# HackJrGameController-v1_0.net
KiCad netlist of a schematic drawn in EAGLE
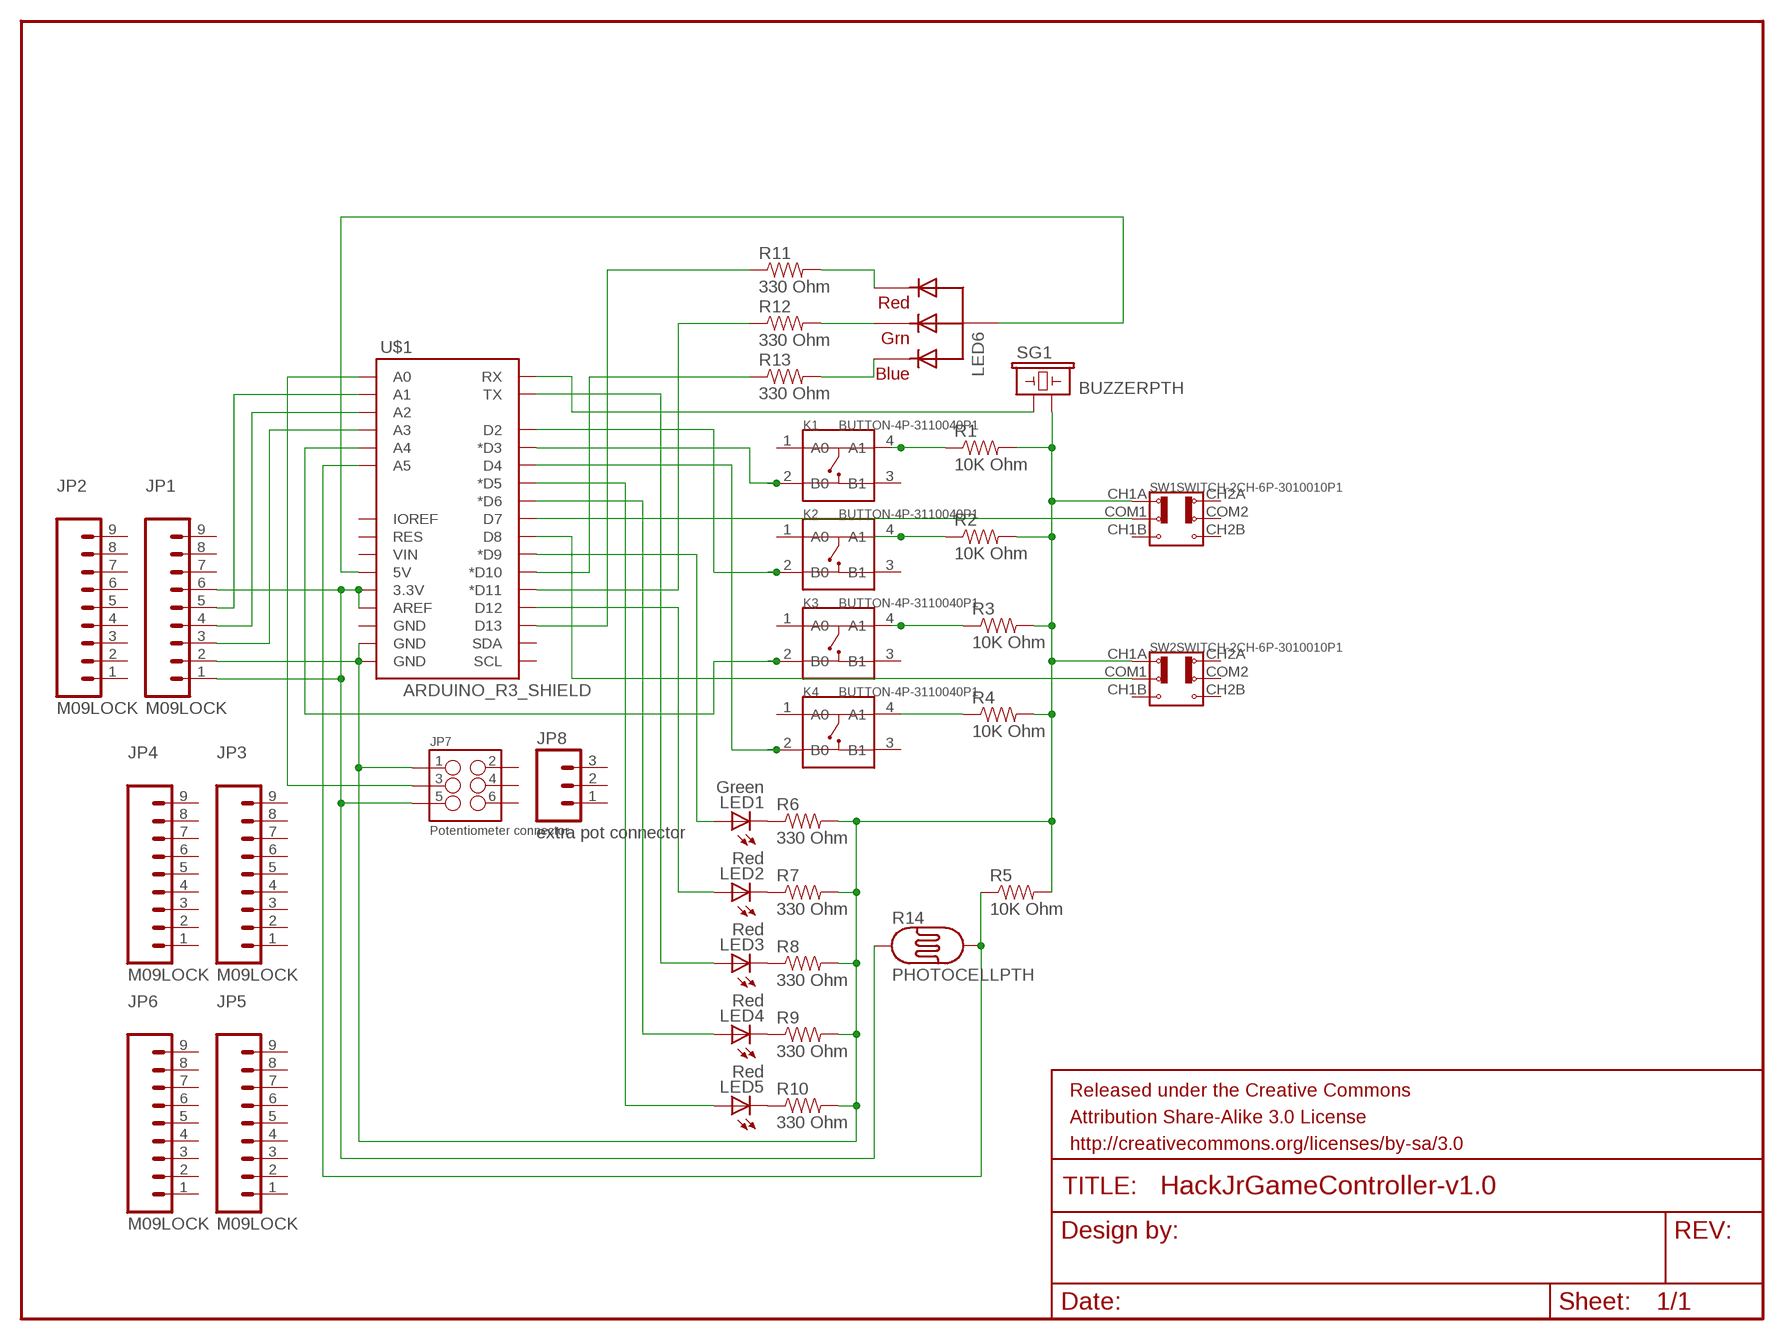
[diagram p0: schematic, sheet 1]

(export (version "E")
  (design (tool "Eeschema 10.0.6"))
  (components
    (comp (ref "FRAME1")
      (value "FRAME-LETTER")
      (footprint "eagle-import:CREATIVE_COMMONS")
      (libsource (lib "eagle-import") (part "FRAME-LETTER"))
    )
    (comp (ref "JP1")
      (value "M09LOCK")
      (footprint "eagle-import:1X09_LOCK")
      (libsource (lib "eagle-import") (part "M09LOCK"))
    )
    (comp (ref "JP2")
      (value "M09LOCK")
      (footprint "eagle-import:1X09_LOCK")
      (libsource (lib "eagle-import") (part "M09LOCK"))
    )
    (comp (ref "JP3")
      (value "M09LOCK")
      (footprint "eagle-import:1X09_LOCK")
      (libsource (lib "eagle-import") (part "M09LOCK"))
    )
    (comp (ref "JP4")
      (value "M09LOCK")
      (footprint "eagle-import:1X09_LOCK")
      (libsource (lib "eagle-import") (part "M09LOCK"))
    )
    (comp (ref "JP5")
      (value "M09LOCK")
      (footprint "eagle-import:1X09_LOCK")
      (libsource (lib "eagle-import") (part "M09LOCK"))
    )
    (comp (ref "JP6")
      (value "M09LOCK")
      (footprint "eagle-import:1X09_LOCK")
      (libsource (lib "eagle-import") (part "M09LOCK"))
    )
    (comp (ref "JP7")
      (value "Potentiometer connector")
      (footprint "eagle-import:2X3-NS")
      (libsource (lib "eagle-import") (part "M03X2NO_SILK"))
    )
    (comp (ref "JP8")
      (value "extra pot connector")
      (footprint "eagle-import:1X03_NO_SILK")
      (libsource (lib "eagle-import") (part "M031X03_NO_SILK"))
    )
    (comp (ref "K1")
      (value "BUTTON-4P-3110040P1")
      (footprint "eagle-import:4P-6.0X6.0X5.0H")
      (libsource (lib "eagle-import") (part "BUTTON-4P-3110040P1"))
    )
    (comp (ref "K2")
      (value "BUTTON-4P-3110040P1")
      (footprint "eagle-import:4P-6.0X6.0X5.0H")
      (libsource (lib "eagle-import") (part "BUTTON-4P-3110040P1"))
    )
    (comp (ref "K3")
      (value "BUTTON-4P-3110040P1")
      (footprint "eagle-import:4P-6.0X6.0X5.0H")
      (libsource (lib "eagle-import") (part "BUTTON-4P-3110040P1"))
    )
    (comp (ref "K4")
      (value "BUTTON-4P-3110040P1")
      (footprint "eagle-import:4P-6.0X6.0X5.0H")
      (libsource (lib "eagle-import") (part "BUTTON-4P-3110040P1"))
    )
    (comp (ref "LED1")
      (value "Green")
      (footprint "eagle-import:LED5MM")
      (libsource (lib "eagle-import") (part "LED5MM"))
    )
    (comp (ref "LED2")
      (value "Red")
      (footprint "eagle-import:LED5MM")
      (libsource (lib "eagle-import") (part "LED5MM"))
    )
    (comp (ref "LED3")
      (value "Red")
      (footprint "eagle-import:LED5MM")
      (libsource (lib "eagle-import") (part "LED5MM"))
    )
    (comp (ref "LED4")
      (value "Red")
      (footprint "eagle-import:LED5MM")
      (libsource (lib "eagle-import") (part "LED5MM"))
    )
    (comp (ref "LED5")
      (value "Red")
      (footprint "eagle-import:LED5MM")
      (libsource (lib "eagle-import") (part "LED5MM"))
    )
    (comp (ref "LED6")
      (value "RGBLED_CA-5MM")
      (footprint "eagle-import:LED5MMRGB")
      (libsource (lib "eagle-import") (part "RGBLED_CA-5MM"))
    )
    (comp (ref "R1")
      (value "10K Ohm")
      (footprint "eagle-import:AXIAL-0.3-KIT")
      (libsource (lib "eagle-import") (part "10KOHM1/6W5%(PTH)KIT"))
    )
    (comp (ref "R2")
      (value "10K Ohm")
      (footprint "eagle-import:AXIAL-0.3-KIT")
      (libsource (lib "eagle-import") (part "10KOHM1/6W5%(PTH)KIT"))
    )
    (comp (ref "R3")
      (value "10K Ohm")
      (footprint "eagle-import:AXIAL-0.3-KIT")
      (libsource (lib "eagle-import") (part "10KOHM1/6W5%(PTH)KIT"))
    )
    (comp (ref "R4")
      (value "10K Ohm")
      (footprint "eagle-import:AXIAL-0.3-KIT")
      (libsource (lib "eagle-import") (part "10KOHM1/6W5%(PTH)KIT"))
    )
    (comp (ref "R5")
      (value "10K Ohm")
      (footprint "eagle-import:AXIAL-0.3-KIT")
      (libsource (lib "eagle-import") (part "10KOHM1/6W5%(PTH)KIT"))
    )
    (comp (ref "R6")
      (value "330 Ohm")
      (footprint "eagle-import:AXIAL-0.3-KIT")
      (libsource (lib "eagle-import") (part "RESISTORKIT"))
    )
    (comp (ref "R7")
      (value "330 Ohm")
      (footprint "eagle-import:AXIAL-0.3-KIT")
      (libsource (lib "eagle-import") (part "RESISTORKIT"))
    )
    (comp (ref "R8")
      (value "330 Ohm")
      (footprint "eagle-import:AXIAL-0.3-KIT")
      (libsource (lib "eagle-import") (part "RESISTORKIT"))
    )
    (comp (ref "R9")
      (value "330 Ohm")
      (footprint "eagle-import:AXIAL-0.3-KIT")
      (libsource (lib "eagle-import") (part "RESISTORKIT"))
    )
    (comp (ref "R10")
      (value "330 Ohm")
      (footprint "eagle-import:AXIAL-0.3-KIT")
      (libsource (lib "eagle-import") (part "RESISTORKIT"))
    )
    (comp (ref "R11")
      (value "330 Ohm")
      (footprint "eagle-import:AXIAL-0.3-KIT")
      (libsource (lib "eagle-import") (part "RESISTORKIT"))
    )
    (comp (ref "R12")
      (value "330 Ohm")
      (footprint "eagle-import:AXIAL-0.3-KIT")
      (libsource (lib "eagle-import") (part "RESISTORKIT"))
    )
    (comp (ref "R13")
      (value "330 Ohm")
      (footprint "eagle-import:AXIAL-0.3-KIT")
      (libsource (lib "eagle-import") (part "RESISTORKIT"))
    )
    (comp (ref "R14")
      (value "PHOTOCELLPTH")
      (footprint "eagle-import:PHOTOCELL")
      (libsource (lib "eagle-import") (part "PHOTOCELLPTH"))
    )
    (comp (ref "SG1")
      (value "BUZZERPTH")
      (footprint "eagle-import:BUZZER-12MM")
      (libsource (lib "eagle-import") (part "BUZZERPTH"))
    )
    (comp (ref "SW1")
      (value "SWITCH-2CH-6P-3010010P1")
      (footprint "eagle-import:6P-2CH-2.54-9.1X3.5X3.2+2H")
      (libsource (lib "eagle-import") (part "SWITCH-2CH-6P-3010010P1"))
    )
    (comp (ref "SW2")
      (value "SWITCH-2CH-6P-3010010P1")
      (footprint "eagle-import:6P-2CH-2.54-9.1X3.5X3.2+2H")
      (libsource (lib "eagle-import") (part "SWITCH-2CH-6P-3010010P1"))
    )
    (comp (ref "U$1")
      (value "ARDUINO_R3_SHIELD")
      (footprint "eagle-import:UNO_R3_SHIELD")
      (libsource (lib "eagle-import") (part "ARDUINO_R3_SHIELD"))
    )
  )
  (nets
    (net (code "1") (name "Net-(JP1-Pad3)") (class "Default")
      (node (ref "JP1") (pin "3") (pinfunction "3_3") (pintype "passive"))
      (node (ref "U$1") (pin "A3") (pinfunction "A3_A3") (pintype "bidirectional"))
    )
    (net (code "2") (name "Net-(JP1-Pad4)") (class "Default")
      (node (ref "JP1") (pin "4") (pinfunction "4_4") (pintype "passive"))
      (node (ref "U$1") (pin "A2") (pinfunction "A2_A2") (pintype "bidirectional"))
    )
    (net (code "3") (name "Net-(JP1-Pad5)") (class "Default")
      (node (ref "JP1") (pin "5") (pinfunction "5_5") (pintype "passive"))
      (node (ref "U$1") (pin "A1") (pinfunction "A1_A1") (pintype "bidirectional"))
    )
    (net (code "4") (name "Net-(JP7-Pad3)") (class "Default")
      (node (ref "JP7") (pin "3") (pinfunction "3_3") (pintype "bidirectional"))
      (node (ref "U$1") (pin "A0") (pinfunction "A0_A0") (pintype "bidirectional"))
    )
    (net (code "5") (name "Net-(K1-A1)") (class "Default")
      (node (ref "K1") (pin "4") (pinfunction "A1_4") (pintype "bidirectional"))
      (node (ref "R1") (pin "P$1") (pinfunction "1_P$1") (pintype "passive"))
    )
    (net (code "6") (name "Net-(K1-B0)") (class "Default")
      (node (ref "K1") (pin "2") (pinfunction "B0_2") (pintype "bidirectional"))
      (node (ref "U$1") (pin "D3") (pinfunction "*D3_D3") (pintype "bidirectional"))
    )
    (net (code "7") (name "Net-(K2-A1)") (class "Default")
      (node (ref "K2") (pin "4") (pinfunction "A1_4") (pintype "bidirectional"))
      (node (ref "R2") (pin "P$1") (pinfunction "1_P$1") (pintype "passive"))
    )
    (net (code "8") (name "Net-(K2-B0)") (class "Default")
      (node (ref "K2") (pin "2") (pinfunction "B0_2") (pintype "bidirectional"))
      (node (ref "U$1") (pin "D2") (pinfunction "D2_D2") (pintype "bidirectional"))
    )
    (net (code "9") (name "Net-(K3-A1)") (class "Default")
      (node (ref "K3") (pin "4") (pinfunction "A1_4") (pintype "bidirectional"))
      (node (ref "R3") (pin "P$1") (pinfunction "1_P$1") (pintype "passive"))
    )
    (net (code "10") (name "Net-(K3-B0)") (class "Default")
      (node (ref "K3") (pin "2") (pinfunction "B0_2") (pintype "bidirectional"))
      (node (ref "U$1") (pin "A4") (pinfunction "A4_A4") (pintype "bidirectional"))
    )
    (net (code "11") (name "Net-(K4-A1)") (class "Default")
      (node (ref "K4") (pin "4") (pinfunction "A1_4") (pintype "bidirectional"))
      (node (ref "R4") (pin "P$1") (pinfunction "1_P$1") (pintype "passive"))
    )
    (net (code "12") (name "Net-(K4-B0)") (class "Default")
      (node (ref "K4") (pin "2") (pinfunction "B0_2") (pintype "bidirectional"))
      (node (ref "U$1") (pin "D4") (pinfunction "D4_D4") (pintype "bidirectional"))
    )
    (net (code "13") (name "Net-(LED1-C)") (class "Default")
      (node (ref "LED1") (pin "K") (pinfunction "C_K") (pintype "passive"))
      (node (ref "R6") (pin "P$1") (pinfunction "1_P$1") (pintype "passive"))
    )
    (net (code "14") (name "Net-(LED2-C)") (class "Default")
      (node (ref "LED2") (pin "K") (pinfunction "C_K") (pintype "passive"))
      (node (ref "R7") (pin "P$1") (pinfunction "1_P$1") (pintype "passive"))
    )
    (net (code "15") (name "Net-(LED2-PadA)") (class "Default")
      (node (ref "LED2") (pin "A") (pinfunction "A_A") (pintype "passive"))
      (node (ref "U$1") (pin "D12") (pinfunction "D12_D12") (pintype "bidirectional"))
    )
    (net (code "16") (name "Net-(LED3-C)") (class "Default")
      (node (ref "LED3") (pin "K") (pinfunction "C_K") (pintype "passive"))
      (node (ref "R8") (pin "P$1") (pinfunction "1_P$1") (pintype "passive"))
    )
    (net (code "17") (name "Net-(LED3-PadA)") (class "Default")
      (node (ref "LED3") (pin "A") (pinfunction "A_A") (pintype "passive"))
      (node (ref "U$1") (pin "TX") (pinfunction "TX_TX") (pintype "bidirectional"))
    )
    (net (code "18") (name "Net-(LED4-C)") (class "Default")
      (node (ref "LED4") (pin "K") (pinfunction "C_K") (pintype "passive"))
      (node (ref "R9") (pin "P$1") (pinfunction "1_P$1") (pintype "passive"))
    )
    (net (code "19") (name "Net-(LED5-C)") (class "Default")
      (node (ref "LED5") (pin "K") (pinfunction "C_K") (pintype "passive"))
      (node (ref "R10") (pin "P$1") (pinfunction "1_P$1") (pintype "passive"))
    )
    (net (code "20") (name "Net-(LED6-BLUE)") (class "Default")
      (node (ref "LED6") (pin "4") (pinfunction "BLUE_4") (pintype "bidirectional"))
      (node (ref "R13") (pin "P$2") (pinfunction "2_P$2") (pintype "passive"))
    )
    (net (code "21") (name "Net-(LED6-GREEN)") (class "Default")
      (node (ref "LED6") (pin "3") (pinfunction "GREEN_3") (pintype "bidirectional"))
      (node (ref "R12") (pin "P$2") (pinfunction "2_P$2") (pintype "passive"))
    )
    (net (code "22") (name "Net-(LED6-RED)") (class "Default")
      (node (ref "LED6") (pin "1") (pinfunction "RED_1") (pintype "bidirectional"))
      (node (ref "R11") (pin "P$2") (pinfunction "2_P$2") (pintype "passive"))
    )
    (net (code "23") (name "Net-(LED6-VCC)") (class "Default")
      (node (ref "LED6") (pin "2") (pinfunction "VCC_2") (pintype "bidirectional"))
      (node (ref "U$1") (pin "5V") (pinfunction "5V_5V") (pintype "bidirectional"))
    )
    (net (code "24") (name "Net-(R1-2)") (class "Default")
      (node (ref "JP1") (pin "2") (pinfunction "2_2") (pintype "passive"))
      (node (ref "JP7") (pin "1") (pinfunction "1_1") (pintype "bidirectional"))
      (node (ref "R1") (pin "P$2") (pinfunction "2_P$2") (pintype "passive"))
      (node (ref "R10") (pin "P$2") (pinfunction "2_P$2") (pintype "passive"))
      (node (ref "R2") (pin "P$2") (pinfunction "2_P$2") (pintype "passive"))
      (node (ref "R3") (pin "P$2") (pinfunction "2_P$2") (pintype "passive"))
      (node (ref "R4") (pin "P$2") (pinfunction "2_P$2") (pintype "passive"))
      (node (ref "R5") (pin "P$2") (pinfunction "2_P$2") (pintype "passive"))
      (node (ref "R6") (pin "P$2") (pinfunction "2_P$2") (pintype "passive"))
      (node (ref "R7") (pin "P$2") (pinfunction "2_P$2") (pintype "passive"))
      (node (ref "R8") (pin "P$2") (pinfunction "2_P$2") (pintype "passive"))
      (node (ref "R9") (pin "P$2") (pinfunction "2_P$2") (pintype "passive"))
      (node (ref "SG1") (pin "-") (pinfunction "2_-") (pintype "passive"))
      (node (ref "SW1") (pin "CH1A") (pinfunction "CH1A_CH1A") (pintype "bidirectional"))
      (node (ref "SW2") (pin "CH1A") (pinfunction "CH1A_CH1A") (pintype "bidirectional"))
      (node (ref "U$1") (pin "GND@0") (pinfunction "GND_GND@0") (pintype "bidirectional"))
      (node (ref "U$1") (pin "GND@1") (pinfunction "GND_GND@1") (pintype "bidirectional"))
    )
    (net (code "25") (name "Net-(R11-1)") (class "Default")
      (node (ref "R11") (pin "P$1") (pinfunction "1_P$1") (pintype "passive"))
      (node (ref "U$1") (pin "D13") (pinfunction "D13_D13") (pintype "bidirectional"))
    )
    (net (code "26") (name "Net-(R12-1)") (class "Default")
      (node (ref "R12") (pin "P$1") (pinfunction "1_P$1") (pintype "passive"))
      (node (ref "U$1") (pin "D11") (pinfunction "*D11_D11") (pintype "bidirectional"))
    )
    (net (code "27") (name "Net-(R13-1)") (class "Default")
      (node (ref "R13") (pin "P$1") (pinfunction "1_P$1") (pintype "passive"))
      (node (ref "U$1") (pin "D10") (pinfunction "*D10_D10") (pintype "bidirectional"))
    )
    (net (code "28") (name "Net-(R14-P$1)") (class "Default")
      (node (ref "JP1") (pin "1") (pinfunction "1_1") (pintype "passive"))
      (node (ref "JP1") (pin "6") (pinfunction "6_6") (pintype "passive"))
      (node (ref "JP7") (pin "5") (pinfunction "5_5") (pintype "bidirectional"))
      (node (ref "R14") (pin "1") (pinfunction "P$1_1") (pintype "bidirectional"))
      (node (ref "U$1") (pin "3.3V") (pinfunction "3.3V_3.3V") (pintype "bidirectional"))
      (node (ref "U$1") (pin "AREF") (pinfunction "AREF_AREF") (pintype "bidirectional"))
    )
    (net (code "29") (name "Net-(R14-P$2)") (class "Default")
      (node (ref "R14") (pin "2") (pinfunction "P$2_2") (pintype "bidirectional"))
      (node (ref "R5") (pin "P$1") (pinfunction "1_P$1") (pintype "passive"))
      (node (ref "U$1") (pin "A5") (pinfunction "A5_A5") (pintype "bidirectional"))
    )
    (net (code "30") (name "Net-(SG1-1)") (class "Default")
      (node (ref "SG1") (pin "+") (pinfunction "1_+") (pintype "passive"))
      (node (ref "U$1") (pin "RX") (pinfunction "RX_RX") (pintype "bidirectional"))
    )
    (net (code "31") (name "Net-(SW1-PadCOM1)") (class "Default")
      (node (ref "SW1") (pin "COM1") (pinfunction "COM1_COM1") (pintype "bidirectional"))
      (node (ref "U$1") (pin "D7") (pinfunction "D7_D7") (pintype "bidirectional"))
    )
    (net (code "32") (name "Net-(SW2-PadCOM1)") (class "Default")
      (node (ref "SW2") (pin "COM1") (pinfunction "COM1_COM1") (pintype "bidirectional"))
      (node (ref "U$1") (pin "D8") (pinfunction "D8_D8") (pintype "bidirectional"))
    )
    (net (code "33") (name "Net-(U$1-*D5)") (class "Default")
      (node (ref "LED5") (pin "A") (pinfunction "A_A") (pintype "passive"))
      (node (ref "U$1") (pin "D5") (pinfunction "*D5_D5") (pintype "bidirectional"))
    )
    (net (code "34") (name "Net-(U$1-*D6)") (class "Default")
      (node (ref "LED4") (pin "A") (pinfunction "A_A") (pintype "passive"))
      (node (ref "U$1") (pin "D6") (pinfunction "*D6_D6") (pintype "bidirectional"))
    )
    (net (code "35") (name "Net-(U$1-*D9)") (class "Default")
      (node (ref "LED1") (pin "A") (pinfunction "A_A") (pintype "passive"))
      (node (ref "U$1") (pin "D9") (pinfunction "*D9_D9") (pintype "bidirectional"))
    )
    (net (code "36") (name "unconnected-(JP1-Pad7)") (class "Default")
      (node (ref "JP1") (pin "7") (pinfunction "7_7") (pintype "passive"))
    )
    (net (code "37") (name "unconnected-(JP1-Pad8)") (class "Default")
      (node (ref "JP1") (pin "8") (pinfunction "8_8") (pintype "passive"))
    )
    (net (code "38") (name "unconnected-(JP1-Pad9)") (class "Default")
      (node (ref "JP1") (pin "9") (pinfunction "9_9") (pintype "passive"))
    )
    (net (code "39") (name "unconnected-(JP2-Pad1)") (class "Default")
      (node (ref "JP2") (pin "1") (pinfunction "1_1") (pintype "passive"))
    )
    (net (code "40") (name "unconnected-(JP2-Pad2)") (class "Default")
      (node (ref "JP2") (pin "2") (pinfunction "2_2") (pintype "passive"))
    )
    (net (code "41") (name "unconnected-(JP2-Pad3)") (class "Default")
      (node (ref "JP2") (pin "3") (pinfunction "3_3") (pintype "passive"))
    )
    (net (code "42") (name "unconnected-(JP2-Pad4)") (class "Default")
      (node (ref "JP2") (pin "4") (pinfunction "4_4") (pintype "passive"))
    )
    (net (code "43") (name "unconnected-(JP2-Pad5)") (class "Default")
      (node (ref "JP2") (pin "5") (pinfunction "5_5") (pintype "passive"))
    )
    (net (code "44") (name "unconnected-(JP2-Pad6)") (class "Default")
      (node (ref "JP2") (pin "6") (pinfunction "6_6") (pintype "passive"))
    )
    (net (code "45") (name "unconnected-(JP2-Pad7)") (class "Default")
      (node (ref "JP2") (pin "7") (pinfunction "7_7") (pintype "passive"))
    )
    (net (code "46") (name "unconnected-(JP2-Pad8)") (class "Default")
      (node (ref "JP2") (pin "8") (pinfunction "8_8") (pintype "passive"))
    )
    (net (code "47") (name "unconnected-(JP2-Pad9)") (class "Default")
      (node (ref "JP2") (pin "9") (pinfunction "9_9") (pintype "passive"))
    )
    (net (code "48") (name "unconnected-(JP3-Pad1)") (class "Default")
      (node (ref "JP3") (pin "1") (pinfunction "1_1") (pintype "passive"))
    )
    (net (code "49") (name "unconnected-(JP3-Pad2)") (class "Default")
      (node (ref "JP3") (pin "2") (pinfunction "2_2") (pintype "passive"))
    )
    (net (code "50") (name "unconnected-(JP3-Pad3)") (class "Default")
      (node (ref "JP3") (pin "3") (pinfunction "3_3") (pintype "passive"))
    )
    (net (code "51") (name "unconnected-(JP3-Pad4)") (class "Default")
      (node (ref "JP3") (pin "4") (pinfunction "4_4") (pintype "passive"))
    )
    (net (code "52") (name "unconnected-(JP3-Pad5)") (class "Default")
      (node (ref "JP3") (pin "5") (pinfunction "5_5") (pintype "passive"))
    )
    (net (code "53") (name "unconnected-(JP3-Pad6)") (class "Default")
      (node (ref "JP3") (pin "6") (pinfunction "6_6") (pintype "passive"))
    )
    (net (code "54") (name "unconnected-(JP3-Pad7)") (class "Default")
      (node (ref "JP3") (pin "7") (pinfunction "7_7") (pintype "passive"))
    )
    (net (code "55") (name "unconnected-(JP3-Pad8)") (class "Default")
      (node (ref "JP3") (pin "8") (pinfunction "8_8") (pintype "passive"))
    )
    (net (code "56") (name "unconnected-(JP3-Pad9)") (class "Default")
      (node (ref "JP3") (pin "9") (pinfunction "9_9") (pintype "passive"))
    )
    (net (code "57") (name "unconnected-(JP4-Pad1)") (class "Default")
      (node (ref "JP4") (pin "1") (pinfunction "1_1") (pintype "passive"))
    )
    (net (code "58") (name "unconnected-(JP4-Pad2)") (class "Default")
      (node (ref "JP4") (pin "2") (pinfunction "2_2") (pintype "passive"))
    )
    (net (code "59") (name "unconnected-(JP4-Pad3)") (class "Default")
      (node (ref "JP4") (pin "3") (pinfunction "3_3") (pintype "passive"))
    )
    (net (code "60") (name "unconnected-(JP4-Pad4)") (class "Default")
      (node (ref "JP4") (pin "4") (pinfunction "4_4") (pintype "passive"))
    )
    (net (code "61") (name "unconnected-(JP4-Pad5)") (class "Default")
      (node (ref "JP4") (pin "5") (pinfunction "5_5") (pintype "passive"))
    )
    (net (code "62") (name "unconnected-(JP4-Pad6)") (class "Default")
      (node (ref "JP4") (pin "6") (pinfunction "6_6") (pintype "passive"))
    )
    (net (code "63") (name "unconnected-(JP4-Pad7)") (class "Default")
      (node (ref "JP4") (pin "7") (pinfunction "7_7") (pintype "passive"))
    )
    (net (code "64") (name "unconnected-(JP4-Pad8)") (class "Default")
      (node (ref "JP4") (pin "8") (pinfunction "8_8") (pintype "passive"))
    )
    (net (code "65") (name "unconnected-(JP4-Pad9)") (class "Default")
      (node (ref "JP4") (pin "9") (pinfunction "9_9") (pintype "passive"))
    )
    (net (code "66") (name "unconnected-(JP5-Pad1)") (class "Default")
      (node (ref "JP5") (pin "1") (pinfunction "1_1") (pintype "passive"))
    )
    (net (code "67") (name "unconnected-(JP5-Pad2)") (class "Default")
      (node (ref "JP5") (pin "2") (pinfunction "2_2") (pintype "passive"))
    )
    (net (code "68") (name "unconnected-(JP5-Pad3)") (class "Default")
      (node (ref "JP5") (pin "3") (pinfunction "3_3") (pintype "passive"))
    )
    (net (code "69") (name "unconnected-(JP5-Pad4)") (class "Default")
      (node (ref "JP5") (pin "4") (pinfunction "4_4") (pintype "passive"))
    )
    (net (code "70") (name "unconnected-(JP5-Pad5)") (class "Default")
      (node (ref "JP5") (pin "5") (pinfunction "5_5") (pintype "passive"))
    )
    (net (code "71") (name "unconnected-(JP5-Pad6)") (class "Default")
      (node (ref "JP5") (pin "6") (pinfunction "6_6") (pintype "passive"))
    )
    (net (code "72") (name "unconnected-(JP5-Pad7)") (class "Default")
      (node (ref "JP5") (pin "7") (pinfunction "7_7") (pintype "passive"))
    )
    (net (code "73") (name "unconnected-(JP5-Pad8)") (class "Default")
      (node (ref "JP5") (pin "8") (pinfunction "8_8") (pintype "passive"))
    )
    (net (code "74") (name "unconnected-(JP5-Pad9)") (class "Default")
      (node (ref "JP5") (pin "9") (pinfunction "9_9") (pintype "passive"))
    )
    (net (code "75") (name "unconnected-(JP6-Pad1)") (class "Default")
      (node (ref "JP6") (pin "1") (pinfunction "1_1") (pintype "passive"))
    )
    (net (code "76") (name "unconnected-(JP6-Pad2)") (class "Default")
      (node (ref "JP6") (pin "2") (pinfunction "2_2") (pintype "passive"))
    )
    (net (code "77") (name "unconnected-(JP6-Pad3)") (class "Default")
      (node (ref "JP6") (pin "3") (pinfunction "3_3") (pintype "passive"))
    )
    (net (code "78") (name "unconnected-(JP6-Pad4)") (class "Default")
      (node (ref "JP6") (pin "4") (pinfunction "4_4") (pintype "passive"))
    )
    (net (code "79") (name "unconnected-(JP6-Pad5)") (class "Default")
      (node (ref "JP6") (pin "5") (pinfunction "5_5") (pintype "passive"))
    )
    (net (code "80") (name "unconnected-(JP6-Pad6)") (class "Default")
      (node (ref "JP6") (pin "6") (pinfunction "6_6") (pintype "passive"))
    )
    (net (code "81") (name "unconnected-(JP6-Pad7)") (class "Default")
      (node (ref "JP6") (pin "7") (pinfunction "7_7") (pintype "passive"))
    )
    (net (code "82") (name "unconnected-(JP6-Pad8)") (class "Default")
      (node (ref "JP6") (pin "8") (pinfunction "8_8") (pintype "passive"))
    )
    (net (code "83") (name "unconnected-(JP6-Pad9)") (class "Default")
      (node (ref "JP6") (pin "9") (pinfunction "9_9") (pintype "passive"))
    )
    (net (code "84") (name "unconnected-(JP7-Pad2)") (class "Default")
      (node (ref "JP7") (pin "2") (pinfunction "2_2") (pintype "bidirectional"))
    )
    (net (code "85") (name "unconnected-(JP7-Pad4)") (class "Default")
      (node (ref "JP7") (pin "4") (pinfunction "4_4") (pintype "bidirectional"))
    )
    (net (code "86") (name "unconnected-(JP7-Pad6)") (class "Default")
      (node (ref "JP7") (pin "6") (pinfunction "6_6") (pintype "bidirectional"))
    )
    (net (code "87") (name "unconnected-(JP8-Pad1)") (class "Default")
      (node (ref "JP8") (pin "1") (pinfunction "1_1") (pintype "passive"))
    )
    (net (code "88") (name "unconnected-(JP8-Pad2)") (class "Default")
      (node (ref "JP8") (pin "2") (pinfunction "2_2") (pintype "passive"))
    )
    (net (code "89") (name "unconnected-(JP8-Pad3)") (class "Default")
      (node (ref "JP8") (pin "3") (pinfunction "3_3") (pintype "passive"))
    )
    (net (code "90") (name "unconnected-(K1-A0-Pad1)") (class "Default")
      (node (ref "K1") (pin "1") (pinfunction "A0_1") (pintype "bidirectional"))
    )
    (net (code "91") (name "unconnected-(K1-B1-Pad3)") (class "Default")
      (node (ref "K1") (pin "3") (pinfunction "B1_3") (pintype "bidirectional"))
    )
    (net (code "92") (name "unconnected-(K2-A0-Pad1)") (class "Default")
      (node (ref "K2") (pin "1") (pinfunction "A0_1") (pintype "bidirectional"))
    )
    (net (code "93") (name "unconnected-(K2-B1-Pad3)") (class "Default")
      (node (ref "K2") (pin "3") (pinfunction "B1_3") (pintype "bidirectional"))
    )
    (net (code "94") (name "unconnected-(K3-A0-Pad1)") (class "Default")
      (node (ref "K3") (pin "1") (pinfunction "A0_1") (pintype "bidirectional"))
    )
    (net (code "95") (name "unconnected-(K3-B1-Pad3)") (class "Default")
      (node (ref "K3") (pin "3") (pinfunction "B1_3") (pintype "bidirectional"))
    )
    (net (code "96") (name "unconnected-(K4-A0-Pad1)") (class "Default")
      (node (ref "K4") (pin "1") (pinfunction "A0_1") (pintype "bidirectional"))
    )
    (net (code "97") (name "unconnected-(K4-B1-Pad3)") (class "Default")
      (node (ref "K4") (pin "3") (pinfunction "B1_3") (pintype "bidirectional"))
    )
    (net (code "98") (name "unconnected-(SW1-PadCH1B)") (class "Default")
      (node (ref "SW1") (pin "CH1B") (pinfunction "CH1B_CH1B") (pintype "bidirectional"))
    )
    (net (code "99") (name "unconnected-(SW1-PadCH2A)") (class "Default")
      (node (ref "SW1") (pin "CH2A") (pinfunction "CH2A_CH2A") (pintype "bidirectional"))
    )
    (net (code "100") (name "unconnected-(SW1-PadCH2B)") (class "Default")
      (node (ref "SW1") (pin "CH2B") (pinfunction "CH2B_CH2B") (pintype "bidirectional"))
    )
    (net (code "101") (name "unconnected-(SW1-PadCOM2)") (class "Default")
      (node (ref "SW1") (pin "COM2") (pinfunction "COM2_COM2") (pintype "bidirectional"))
    )
    (net (code "102") (name "unconnected-(SW2-PadCH1B)") (class "Default")
      (node (ref "SW2") (pin "CH1B") (pinfunction "CH1B_CH1B") (pintype "bidirectional"))
    )
    (net (code "103") (name "unconnected-(SW2-PadCH2A)") (class "Default")
      (node (ref "SW2") (pin "CH2A") (pinfunction "CH2A_CH2A") (pintype "bidirectional"))
    )
    (net (code "104") (name "unconnected-(SW2-PadCH2B)") (class "Default")
      (node (ref "SW2") (pin "CH2B") (pinfunction "CH2B_CH2B") (pintype "bidirectional"))
    )
    (net (code "105") (name "unconnected-(SW2-PadCOM2)") (class "Default")
      (node (ref "SW2") (pin "COM2") (pinfunction "COM2_COM2") (pintype "bidirectional"))
    )
    (net (code "106") (name "unconnected-(U$1-GND-PadGND@2)") (class "Default")
      (node (ref "U$1") (pin "GND@2") (pinfunction "GND_GND@2") (pintype "bidirectional"))
    )
    (net (code "107") (name "unconnected-(U$1-PadIOREF)") (class "Default")
      (node (ref "U$1") (pin "IOREF") (pinfunction "IOREF_IOREF") (pintype "bidirectional"))
    )
    (net (code "108") (name "unconnected-(U$1-PadRES)") (class "Default")
      (node (ref "U$1") (pin "RES") (pinfunction "RES_RES") (pintype "bidirectional"))
    )
    (net (code "109") (name "unconnected-(U$1-PadSCL)") (class "Default")
      (node (ref "U$1") (pin "SCL") (pinfunction "SCL_SCL") (pintype "bidirectional"))
    )
    (net (code "110") (name "unconnected-(U$1-PadSDA)") (class "Default")
      (node (ref "U$1") (pin "SDA") (pinfunction "SDA_SDA") (pintype "bidirectional"))
    )
    (net (code "111") (name "unconnected-(U$1-PadVIN)") (class "Default")
      (node (ref "U$1") (pin "VIN") (pinfunction "VIN_VIN") (pintype "bidirectional"))
    )
  )
)
